# OscMotherboard.net
KiCad netlist of a schematic drawn in Altium Designer
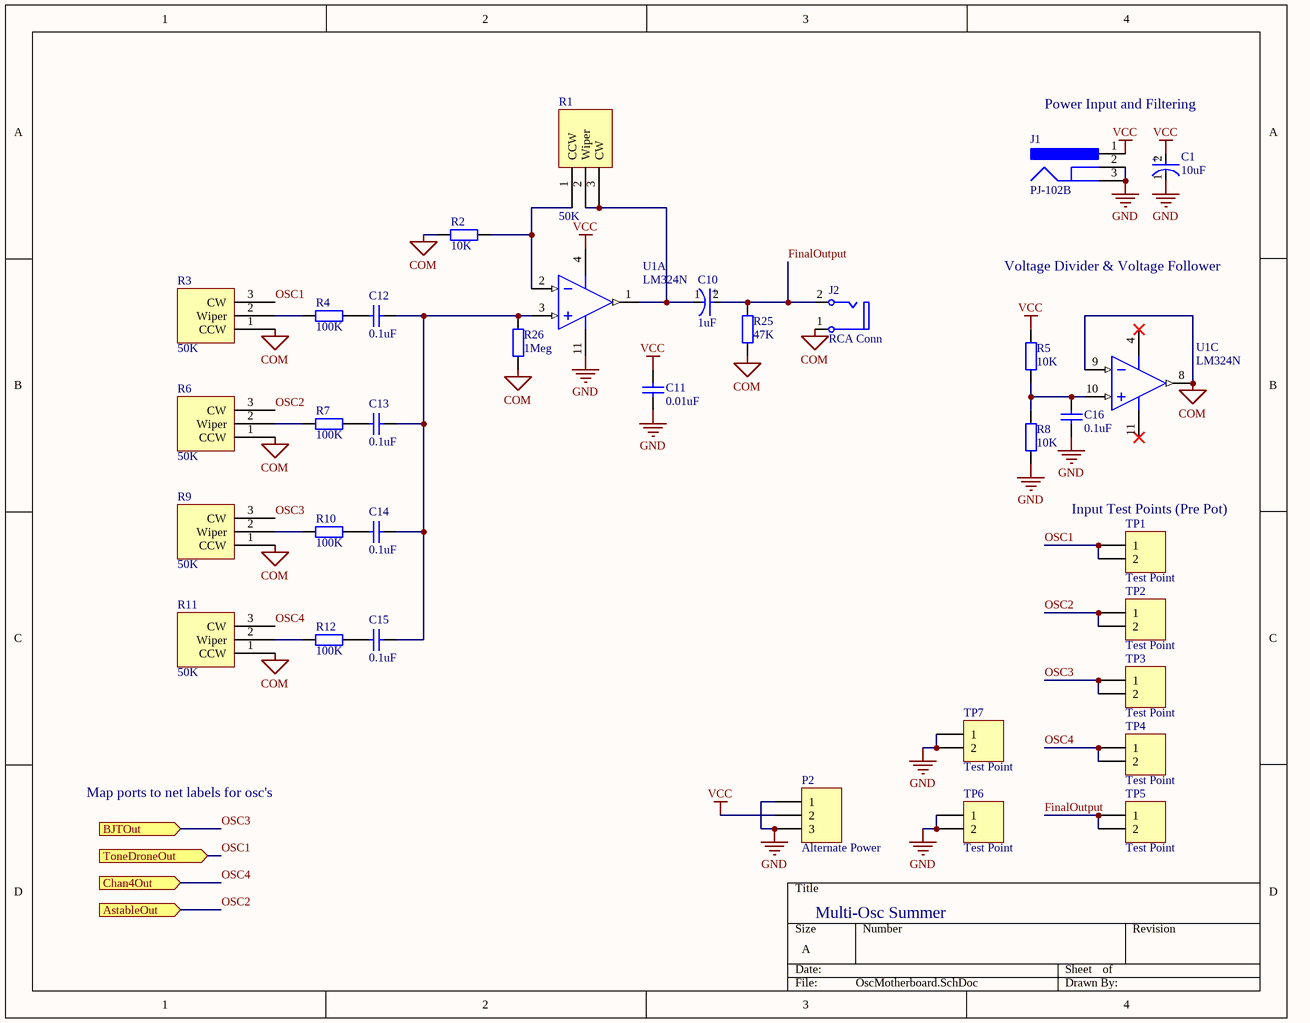
[diagram p0: OscMotherboard.SchDoc]

(export (version "E")
  (design (tool "Eeschema 10.0.6"))
  (components
    (comp (ref "C1")
      (value "10uF")
      (footprint "FP-ESLE3-MFG")
      (description "CAP ALUM 10UF 20% 100V THRU HOLE")
      (fields (field (name "TOLERANCE") "20%") (field (name "MANUFACTURER PART NUMBER") "ESL106M100AE3AA"))
      (libsource (lib "Altium Content Vault") (part "cf48714ba7e38822c1575c7ec0b6d1f"))
    )
    (comp (ref "C10")
      (value "1uF")
      (footprint "FP-ESLE3-MFG")
      (description "CAP ALUM 10UF 20% 100V THRU HOLE")
      (fields (field (name "TOLERANCE") "20%") (field (name "MANUFACTURER PART NUMBER") "ESL106M100AE3AA"))
      (libsource (lib "Altium Content Vault") (part "cf48714ba7e38822c1575c7ec0b6d1f"))
    )
    (comp (ref "C11")
      (value "0.01uF")
      (footprint "KEMT-C315-THT-2")
      (description "Capacitor, Ceramic, 0.01 uF, +/- 10%, 100 V, X7R, -55 to 125 degC, 2-Pin THD, RoHS, Bulk")
      (libsource (lib "Altium Content Vault") (part "CAP-NP-2"))
    )
    (comp (ref "C12")
      (value "0.1uF")
      (footprint "KEMT-C315-THT-2")
      (description "Capacitor, Ceramic, 0.01 uF, +/- 10%, 100 V, X7R, -55 to 125 degC, 2-Pin THD, RoHS, Bulk")
      (libsource (lib "Altium Content Vault") (part "CAP-NP-2"))
    )
    (comp (ref "C13")
      (value "0.1uF")
      (footprint "KEMT-C315-THT-2")
      (description "Capacitor, Ceramic, 0.01 uF, +/- 10%, 100 V, X7R, -55 to 125 degC, 2-Pin THD, RoHS, Bulk")
      (libsource (lib "Altium Content Vault") (part "CAP-NP-2"))
    )
    (comp (ref "C14")
      (value "0.1uF")
      (footprint "KEMT-C315-THT-2")
      (description "Capacitor, Ceramic, 0.01 uF, +/- 10%, 100 V, X7R, -55 to 125 degC, 2-Pin THD, RoHS, Bulk")
      (libsource (lib "Altium Content Vault") (part "CAP-NP-2"))
    )
    (comp (ref "C15")
      (value "0.1uF")
      (footprint "KEMT-C315-THT-2")
      (description "Capacitor, Ceramic, 0.01 uF, +/- 10%, 100 V, X7R, -55 to 125 degC, 2-Pin THD, RoHS, Bulk")
      (libsource (lib "Altium Content Vault") (part "CAP-NP-2"))
    )
    (comp (ref "C16")
      (value "0.1uF")
      (footprint "KEMT-C315-THT-2")
      (description "Capacitor, Ceramic, 0.01 uF, +/- 10%, 100 V, X7R, -55 to 125 degC, 2-Pin THD, RoHS, Bulk")
      (libsource (lib "Altium Content Vault") (part "CAP-NP-2"))
    )
    (comp (ref "J1")
      (value "PJ-102B")
      (footprint "CUI-PJ-102B_V")
      (fields (field (name "MANUFACTURER") "CUIInc."))
      (libsource (lib "Altium Content Vault") (part "JACK-2CD3-RN"))
    )
    (comp (ref "J2")
      (value "RCA Conn")
      (footprint "CUI-RCJ-041_V")
      (description "Female RCJ Jack, 2 Position, Height 11.724 mm, Tail Length 4 mm, RoHS, Bulk")
      (libsource (lib "Altium Content Vault") (part "JACK-2CD2"))
    )
    (comp (ref "P2")
      (value "Alternate Power")
      (footprint "HDR1X3")
      (description "Header, 3-Pin")
      (fields (field (name "PUBLISHER") "Altium Limited"))
      (libsource (lib "Miscellaneous Connectors") (part "Header 3"))
    )
    (comp (ref "R1") (value "50K") (footprint "TrimmerPot") (libsource (lib "") (part "TrimmerPot_1")))
    (comp (ref "R2")
      (value "10K")
      (footprint "AXIAL-0.4")
      (description "Resistor")
      (fields (field (name "PUBLISHER") "Altium Limited"))
      (libsource (lib "Miscellaneous Devices") (part "Res2"))
    )
    (comp (ref "R3") (value "50K") (footprint "TrimmerPot") (libsource (lib "Schlib") (part "TrimmerPot")))
    (comp (ref "R4")
      (value "100K")
      (footprint "AXIAL-0.4")
      (description "Resistor")
      (fields (field (name "PUBLISHER") "Altium Limited"))
      (libsource (lib "Miscellaneous Devices") (part "Res2"))
    )
    (comp (ref "R5")
      (value "10K")
      (footprint "AXIAL-0.4")
      (description "Resistor")
      (fields (field (name "PUBLISHER") "Altium Limited"))
      (libsource (lib "") (part "Res2_1"))
    )
    (comp (ref "R6") (value "50K") (footprint "TrimmerPot") (libsource (lib "Schlib") (part "TrimmerPot")))
    (comp (ref "R7")
      (value "100K")
      (footprint "AXIAL-0.4")
      (description "Resistor")
      (fields (field (name "PUBLISHER") "Altium Limited"))
      (libsource (lib "Miscellaneous Devices") (part "Res2"))
    )
    (comp (ref "R8")
      (value "10K")
      (footprint "AXIAL-0.4")
      (description "Resistor")
      (fields (field (name "PUBLISHER") "Altium Limited"))
      (libsource (lib "") (part "Res2_1"))
    )
    (comp (ref "R9") (value "50K") (footprint "TrimmerPot") (libsource (lib "Schlib") (part "TrimmerPot")))
    (comp (ref "R10")
      (value "100K")
      (footprint "AXIAL-0.4")
      (description "Resistor")
      (fields (field (name "PUBLISHER") "Altium Limited"))
      (libsource (lib "Miscellaneous Devices") (part "Res2"))
    )
    (comp (ref "R11") (value "50K") (footprint "TrimmerPot") (libsource (lib "Schlib") (part "TrimmerPot")))
    (comp (ref "R12")
      (value "100K")
      (footprint "AXIAL-0.4")
      (description "Resistor")
      (fields (field (name "PUBLISHER") "Altium Limited"))
      (libsource (lib "Miscellaneous Devices") (part "Res2"))
    )
    (comp (ref "R25")
      (value "47K")
      (footprint "AXIAL-0.4")
      (description "Resistor")
      (fields (field (name "PUBLISHER") "Altium Limited"))
      (libsource (lib "") (part "Res2_1"))
    )
    (comp (ref "R26")
      (value "1Meg")
      (footprint "AXIAL-0.4")
      (description "Resistor")
      (fields (field (name "PUBLISHER") "Altium Limited"))
      (libsource (lib "") (part "Res2_1"))
    )
    (comp (ref "TP1")
      (value "Test Point")
      (footprint "HDR1X2")
      (description "Header, 2-Pin")
      (fields (field (name "PUBLISHER") "Altium Limited"))
      (libsource (lib "Miscellaneous Connectors") (part "Header 2"))
    )
    (comp (ref "TP2")
      (value "Test Point")
      (footprint "HDR1X2")
      (description "Header, 2-Pin")
      (fields (field (name "PUBLISHER") "Altium Limited"))
      (libsource (lib "Miscellaneous Connectors") (part "Header 2"))
    )
    (comp (ref "TP3")
      (value "Test Point")
      (footprint "HDR1X2")
      (description "Header, 2-Pin")
      (fields (field (name "PUBLISHER") "Altium Limited"))
      (libsource (lib "Miscellaneous Connectors") (part "Header 2"))
    )
    (comp (ref "TP4")
      (value "Test Point")
      (footprint "HDR1X2")
      (description "Header, 2-Pin")
      (fields (field (name "PUBLISHER") "Altium Limited"))
      (libsource (lib "Miscellaneous Connectors") (part "Header 2"))
    )
    (comp (ref "TP5")
      (value "Test Point")
      (footprint "HDR1X2")
      (description "Header, 2-Pin")
      (fields (field (name "PUBLISHER") "Altium Limited"))
      (libsource (lib "Miscellaneous Connectors") (part "Header 2"))
    )
    (comp (ref "TP6")
      (value "Test Point")
      (footprint "HDR1X2")
      (description "Header, 2-Pin")
      (fields (field (name "PUBLISHER") "Altium Limited"))
      (libsource (lib "Miscellaneous Connectors") (part "Header 2"))
    )
    (comp (ref "TP7")
      (value "Test Point")
      (footprint "HDR1X2")
      (description "Header, 2-Pin")
      (fields (field (name "PUBLISHER") "Altium Limited"))
      (libsource (lib "Miscellaneous Connectors") (part "Header 2"))
    )
    (comp (ref "U1")
      (value "LM324N")
      (footprint "N0014A")
      (description "Low Power Quad Operational Amplifier, 14-pin MDIP")
      (fields (field (name "MANUFACTURER") "Texas Instruments"))
      (libsource (lib "Altium Content Vault") (part "AMP-OPA-LM124-14"))
    )
  )
  (nets
    (net (code "1") (name "/FinalOutput") (class "Default")
      (node (ref "C10") (pin "2") (pinfunction "A_2") (pintype "passive"))
      (node (ref "J2") (pin "2") (pinfunction "2_2") (pintype "passive"))
      (node (ref "R25") (pin "1") (pinfunction "1_1") (pintype "passive"))
      (node (ref "TP5") (pin "1") (pinfunction "1_1") (pintype "passive"))
      (node (ref "TP5") (pin "2") (pinfunction "2_2") (pintype "passive"))
    )
    (net (code "2") (name "/OSC1") (class "Default")
      (node (ref "R3") (pin "3") (pinfunction "CW_3") (pintype "passive"))
      (node (ref "TP1") (pin "1") (pinfunction "1_1") (pintype "passive"))
      (node (ref "TP1") (pin "2") (pinfunction "2_2") (pintype "passive"))
    )
    (net (code "3") (name "/OSC2") (class "Default")
      (node (ref "R6") (pin "3") (pinfunction "CW_3") (pintype "passive"))
      (node (ref "TP2") (pin "1") (pinfunction "1_1") (pintype "passive"))
      (node (ref "TP2") (pin "2") (pinfunction "2_2") (pintype "passive"))
    )
    (net (code "4") (name "/OSC3") (class "Default")
      (node (ref "R9") (pin "3") (pinfunction "CW_3") (pintype "passive"))
      (node (ref "TP3") (pin "1") (pinfunction "1_1") (pintype "passive"))
      (node (ref "TP3") (pin "2") (pinfunction "2_2") (pintype "passive"))
    )
    (net (code "5") (name "/OSC4") (class "Default")
      (node (ref "R11") (pin "3") (pinfunction "CW_3") (pintype "passive"))
      (node (ref "TP4") (pin "1") (pinfunction "1_1") (pintype "passive"))
      (node (ref "TP4") (pin "2") (pinfunction "2_2") (pintype "passive"))
    )
    (net (code "6") (name "COM") (class "Default")
      (node (ref "J2") (pin "1") (pinfunction "1_1") (pintype "passive"))
      (node (ref "R11") (pin "1") (pinfunction "CCW_1") (pintype "passive"))
      (node (ref "R2") (pin "2") (pinfunction "2_2") (pintype "passive"))
      (node (ref "R25") (pin "2") (pinfunction "2_2") (pintype "passive"))
      (node (ref "R26") (pin "2") (pinfunction "2_2") (pintype "passive"))
      (node (ref "R3") (pin "1") (pinfunction "CCW_1") (pintype "passive"))
      (node (ref "R6") (pin "1") (pinfunction "CCW_1") (pintype "passive"))
      (node (ref "R9") (pin "1") (pinfunction "CCW_1") (pintype "passive"))
      (node (ref "U1") (pin "8") (pinfunction "OUT3_8") (pintype "output"))
      (node (ref "U1") (pin "9") (pinfunction "IN3-_9") (pintype "input"))
    )
    (net (code "7") (name "GND") (class "Default")
      (node (ref "C1") (pin "1") (pinfunction "C_1") (pintype "passive"))
      (node (ref "C11") (pin "2") (pinfunction "2_2") (pintype "passive"))
      (node (ref "C16") (pin "2") (pinfunction "2_2") (pintype "passive"))
      (node (ref "J1") (pin "2") (pinfunction "2_2") (pintype "passive"))
      (node (ref "J1") (pin "3") (pinfunction "3_3") (pintype "passive"))
      (node (ref "P2") (pin "1") (pinfunction "1_1") (pintype "passive"))
      (node (ref "P2") (pin "3") (pinfunction "3_3") (pintype "passive"))
      (node (ref "R8") (pin "2") (pinfunction "2_2") (pintype "passive"))
      (node (ref "TP6") (pin "1") (pinfunction "1_1") (pintype "passive"))
      (node (ref "TP6") (pin "2") (pinfunction "2_2") (pintype "passive"))
      (node (ref "TP7") (pin "1") (pinfunction "1_1") (pintype "passive"))
      (node (ref "TP7") (pin "2") (pinfunction "2_2") (pintype "passive"))
      (node (ref "U1") (pin "11") (pinfunction "GND_11") (pintype "power_in"))
    )
    (net (code "8") (name "Net-(C10-C)") (class "Default")
      (node (ref "C10") (pin "1") (pinfunction "C_1") (pintype "passive"))
      (node (ref "R1") (pin "2") (pinfunction "Wiper_2") (pintype "passive"))
      (node (ref "R1") (pin "3") (pinfunction "CW_3") (pintype "passive"))
      (node (ref "U1") (pin "1") (pinfunction "OUT1_1") (pintype "output"))
    )
    (net (code "9") (name "Net-(C12-Pad2)") (class "Default")
      (node (ref "C12") (pin "2") (pinfunction "2_2") (pintype "passive"))
      (node (ref "R4") (pin "1") (pinfunction "1_1") (pintype "passive"))
    )
    (net (code "10") (name "Net-(C13-Pad2)") (class "Default")
      (node (ref "C13") (pin "2") (pinfunction "2_2") (pintype "passive"))
      (node (ref "R7") (pin "1") (pinfunction "1_1") (pintype "passive"))
    )
    (net (code "11") (name "Net-(C14-Pad2)") (class "Default")
      (node (ref "C14") (pin "2") (pinfunction "2_2") (pintype "passive"))
      (node (ref "R10") (pin "1") (pinfunction "1_1") (pintype "passive"))
    )
    (net (code "12") (name "Net-(C15-Pad2)") (class "Default")
      (node (ref "C15") (pin "2") (pinfunction "2_2") (pintype "passive"))
      (node (ref "R12") (pin "1") (pinfunction "1_1") (pintype "passive"))
    )
    (net (code "13") (name "Net-(R1-CCW)") (class "Default")
      (node (ref "R1") (pin "1") (pinfunction "CCW_1") (pintype "passive"))
      (node (ref "R2") (pin "1") (pinfunction "1_1") (pintype "passive"))
      (node (ref "U1") (pin "2") (pinfunction "IN1-_2") (pintype "input"))
    )
    (net (code "14") (name "Net-(R3-Wiper)") (class "Default")
      (node (ref "R3") (pin "2") (pinfunction "Wiper_2") (pintype "passive"))
      (node (ref "R4") (pin "2") (pinfunction "2_2") (pintype "passive"))
    )
    (net (code "15") (name "Net-(R6-Wiper)") (class "Default")
      (node (ref "R6") (pin "2") (pinfunction "Wiper_2") (pintype "passive"))
      (node (ref "R7") (pin "2") (pinfunction "2_2") (pintype "passive"))
    )
    (net (code "16") (name "Net-(R9-Wiper)") (class "Default")
      (node (ref "R10") (pin "2") (pinfunction "2_2") (pintype "passive"))
      (node (ref "R9") (pin "2") (pinfunction "Wiper_2") (pintype "passive"))
    )
    (net (code "17") (name "Net-(R11-Wiper)") (class "Default")
      (node (ref "R11") (pin "2") (pinfunction "Wiper_2") (pintype "passive"))
      (node (ref "R12") (pin "2") (pinfunction "2_2") (pintype "passive"))
    )
    (net (code "18") (name "Net-(U1A-IN1+)") (class "Default")
      (node (ref "C12") (pin "1") (pinfunction "1_1") (pintype "passive"))
      (node (ref "C13") (pin "1") (pinfunction "1_1") (pintype "passive"))
      (node (ref "C14") (pin "1") (pinfunction "1_1") (pintype "passive"))
      (node (ref "C15") (pin "1") (pinfunction "1_1") (pintype "passive"))
      (node (ref "R26") (pin "1") (pinfunction "1_1") (pintype "passive"))
      (node (ref "U1") (pin "3") (pinfunction "IN1+_3") (pintype "input"))
    )
    (net (code "19") (name "Net-(U1C-IN3+)") (class "Default")
      (node (ref "C16") (pin "1") (pinfunction "1_1") (pintype "passive"))
      (node (ref "R5") (pin "2") (pinfunction "2_2") (pintype "passive"))
      (node (ref "R8") (pin "1") (pinfunction "1_1") (pintype "passive"))
      (node (ref "U1") (pin "10") (pinfunction "IN3+_10") (pintype "input"))
    )
    (net (code "20") (name "VCC") (class "Default")
      (node (ref "C1") (pin "2") (pinfunction "A_2") (pintype "passive"))
      (node (ref "C11") (pin "1") (pinfunction "1_1") (pintype "passive"))
      (node (ref "J1") (pin "1") (pinfunction "1_1") (pintype "passive"))
      (node (ref "P2") (pin "2") (pinfunction "2_2") (pintype "passive"))
      (node (ref "R5") (pin "1") (pinfunction "1_1") (pintype "passive"))
      (node (ref "U1") (pin "4") (pinfunction "V+_4") (pintype "power_in"))
    )
    (net (code "21") (name "unconnected-(U1C-GND-Pad11)") (class "Default")
      (node (ref "U1") (pin "11") (pinfunction "GND_11") (pintype "power_in+no_connect"))
    )
    (net (code "22") (name "unconnected-(U1C-V+-Pad4)") (class "Default")
      (node (ref "U1") (pin "4") (pinfunction "V+_4") (pintype "power_in+no_connect"))
    )
  )
)
